# CPLD.net
KiCad netlist of a schematic drawn in Altium Designer
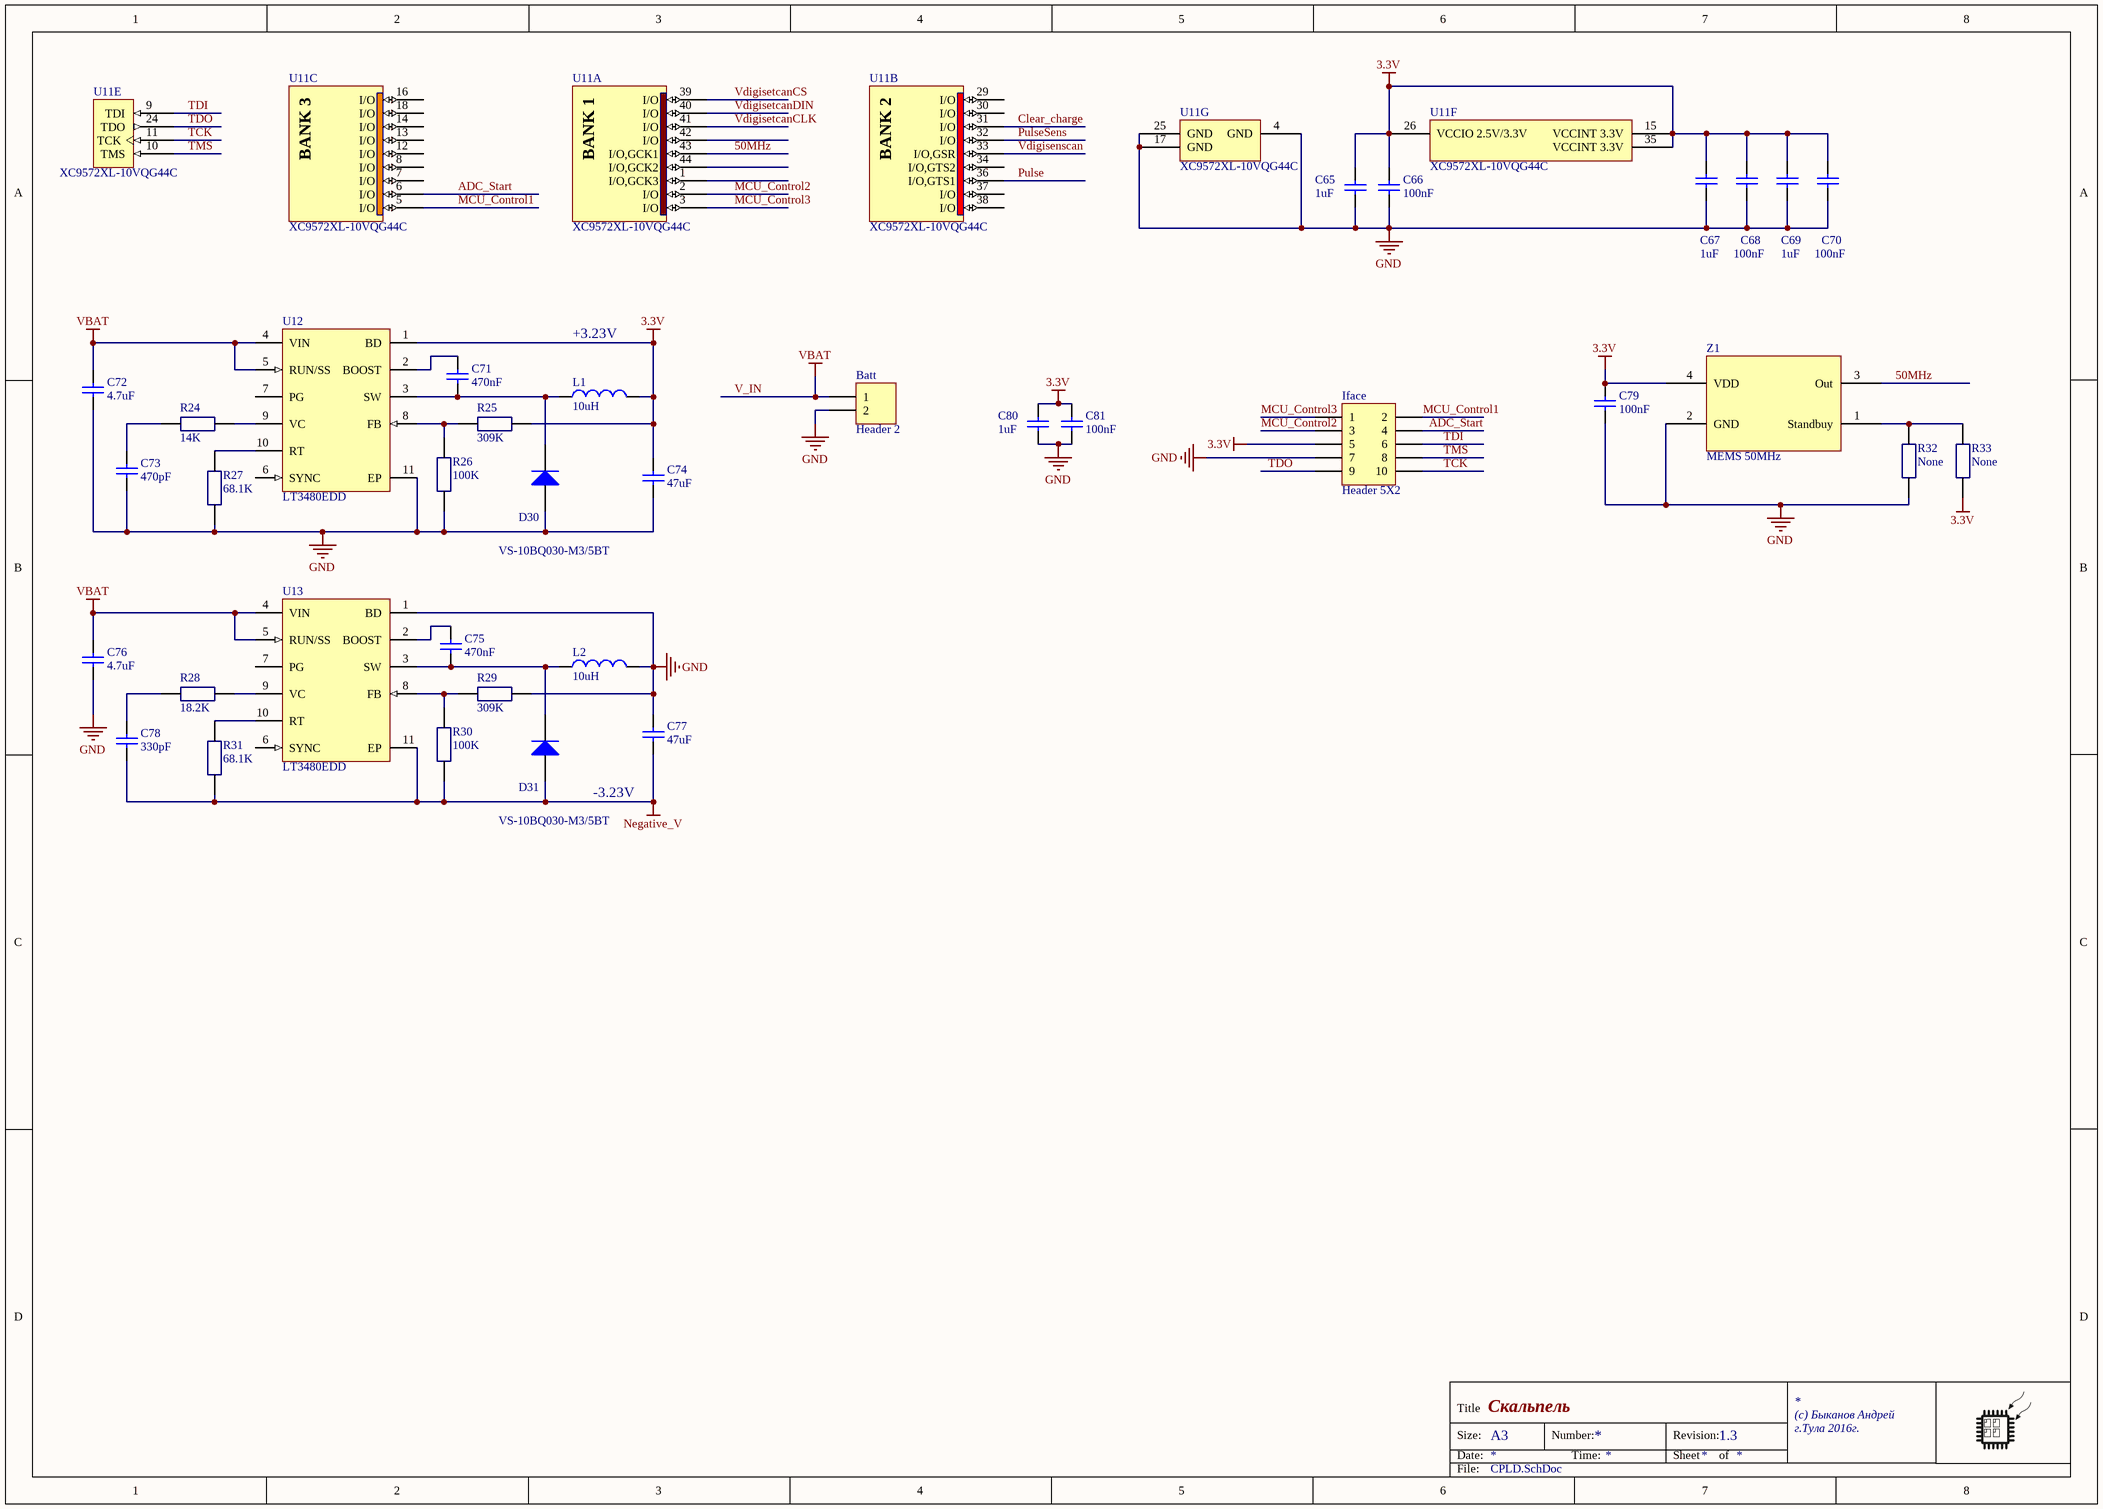
[diagram p0: CPLD.SchDoc]

(export (version "E")
  (design (tool "Eeschema 10.0.6"))
  (components
    (comp (ref "Batt")
      (value "Header 2")
      (footprint "HDR1X2")
      (description "Header, 2-Pin")
      (fields (field (name "PUBLISHER") "Altium Limited"))
      (libsource (lib "Miscellaneous Connectors") (part "Header 2"))
    )
    (comp (ref "C65")
      (value "1uF")
      (footprint "1608[0603]_CAP")
      (description "Capacitor (Semiconductor SIM Model)")
      (fields (field (name "PUBLISHER") "Altium Limited"))
      (libsource (lib "Miscellaneous Devices") (part "Cap Semi"))
    )
    (comp (ref "C66")
      (value "100nF")
      (footprint "1608[0603]_CAP")
      (description "Capacitor (Semiconductor SIM Model)")
      (fields (field (name "PUBLISHER") "Altium Limited"))
      (libsource (lib "Miscellaneous Devices") (part "Cap Semi"))
    )
    (comp (ref "C67")
      (value "1uF")
      (footprint "1608[0603]_CAP")
      (description "Capacitor (Semiconductor SIM Model)")
      (fields (field (name "PUBLISHER") "Altium Limited"))
      (libsource (lib "Miscellaneous Devices") (part "Cap Semi"))
    )
    (comp (ref "C68")
      (value "100nF")
      (footprint "1608[0603]_CAP")
      (description "Capacitor (Semiconductor SIM Model)")
      (fields (field (name "PUBLISHER") "Altium Limited"))
      (libsource (lib "Miscellaneous Devices") (part "Cap Semi"))
    )
    (comp (ref "C69")
      (value "1uF")
      (footprint "1608[0603]_CAP")
      (description "Capacitor (Semiconductor SIM Model)")
      (fields (field (name "PUBLISHER") "Altium Limited"))
      (libsource (lib "Miscellaneous Devices") (part "Cap Semi"))
    )
    (comp (ref "C70")
      (value "100nF")
      (footprint "1608[0603]_CAP")
      (description "Capacitor (Semiconductor SIM Model)")
      (fields (field (name "PUBLISHER") "Altium Limited"))
      (libsource (lib "Miscellaneous Devices") (part "Cap Semi"))
    )
    (comp (ref "C71")
      (value "470nF")
      (footprint "1608[0603]_CAP")
      (description "Capacitor (Semiconductor SIM Model)")
      (fields (field (name "PUBLISHER") "Altium Limited"))
      (libsource (lib "Miscellaneous Devices") (part "Cap Semi"))
    )
    (comp (ref "C72")
      (value "4.7uF")
      (footprint "C1206")
      (description "Capacitor (Semiconductor SIM Model)")
      (fields (field (name "PUBLISHER") "Altium Limited"))
      (libsource (lib "Miscellaneous Devices") (part "Cap Semi"))
    )
    (comp (ref "C73")
      (value "470pF")
      (footprint "1608[0603]_CAP")
      (description "Capacitor (Semiconductor SIM Model)")
      (fields (field (name "PUBLISHER") "Altium Limited"))
      (libsource (lib "Miscellaneous Devices") (part "Cap Semi"))
    )
    (comp (ref "C74")
      (value "47uF")
      (footprint "C1206")
      (description "Capacitor (Semiconductor SIM Model)")
      (fields (field (name "PUBLISHER") "Altium Limited"))
      (libsource (lib "Miscellaneous Devices") (part "Cap Semi"))
    )
    (comp (ref "C75")
      (value "470nF")
      (footprint "1608[0603]_CAP")
      (description "Capacitor (Semiconductor SIM Model)")
      (fields (field (name "PUBLISHER") "Altium Limited"))
      (libsource (lib "Miscellaneous Devices") (part "Cap Semi"))
    )
    (comp (ref "C76")
      (value "4.7uF")
      (footprint "C1206")
      (description "Capacitor (Semiconductor SIM Model)")
      (fields (field (name "PUBLISHER") "Altium Limited"))
      (libsource (lib "Miscellaneous Devices") (part "Cap Semi"))
    )
    (comp (ref "C77")
      (value "47uF")
      (footprint "C1206")
      (description "Capacitor (Semiconductor SIM Model)")
      (fields (field (name "PUBLISHER") "Altium Limited"))
      (libsource (lib "Miscellaneous Devices") (part "Cap Semi"))
    )
    (comp (ref "C78")
      (value "330pF")
      (footprint "1608[0603]_CAP")
      (description "Capacitor (Semiconductor SIM Model)")
      (fields (field (name "PUBLISHER") "Altium Limited"))
      (libsource (lib "Miscellaneous Devices") (part "Cap Semi"))
    )
    (comp (ref "C79")
      (value "100nF")
      (footprint "1608[0603]_CAP")
      (description "Capacitor (Semiconductor SIM Model)")
      (fields (field (name "PUBLISHER") "Altium Limited"))
      (libsource (lib "Miscellaneous Devices") (part "Cap Semi"))
    )
    (comp (ref "C80")
      (value "1uF")
      (footprint "1608[0603]_CAP")
      (description "Capacitor (Semiconductor SIM Model)")
      (fields (field (name "PUBLISHER") "Altium Limited"))
      (libsource (lib "Miscellaneous Devices") (part "Cap Semi"))
    )
    (comp (ref "C81")
      (value "100nF")
      (footprint "1608[0603]_CAP")
      (description "Capacitor (Semiconductor SIM Model)")
      (fields (field (name "PUBLISHER") "Altium Limited"))
      (libsource (lib "Miscellaneous Devices") (part "Cap Semi"))
    )
    (comp (ref "D30")
      (value "VS-10BQ030-M3/5BT")
      (footprint "SMB")
      (description "Default Diode")
      (fields (field (name "PUBLISHER") "Altium Limited"))
      (libsource (lib "Miscellaneous Devices") (part "Diode"))
    )
    (comp (ref "D31")
      (value "VS-10BQ030-M3/5BT")
      (footprint "SMB")
      (description "Default Diode")
      (fields (field (name "PUBLISHER") "Altium Limited"))
      (libsource (lib "Miscellaneous Devices") (part "Diode"))
    )
    (comp (ref "Iface")
      (value "Header 5X2")
      (footprint "HDR2X5")
      (description "Header, 5-Pin, Dual row")
      (fields (field (name "PUBLISHER") "Altium Limited"))
      (libsource (lib "Miscellaneous Connectors") (part "Header 5X2"))
    )
    (comp (ref "L1")
      (value "10uH")
      (footprint "SLF10145")
      (description "Inductor")
      (fields (field (name "PUBLISHER") "Altium Limited"))
      (libsource (lib "Miscellaneous Devices") (part "Inductor"))
    )
    (comp (ref "L2")
      (value "10uH")
      (footprint "SLF10145")
      (description "Inductor")
      (fields (field (name "PUBLISHER") "Altium Limited"))
      (libsource (lib "Miscellaneous Devices") (part "Inductor"))
    )
    (comp (ref "R24")
      (value "14K")
      (footprint "1608[0603]_RES")
      (libsource (lib "Микрон-3") (part "Resistor 0805"))
    )
    (comp (ref "R25")
      (value "309K")
      (footprint "1608[0603]_RES")
      (libsource (lib "Микрон-3") (part "Resistor 0805"))
    )
    (comp (ref "R26")
      (value "100K")
      (footprint "1608[0603]_RES")
      (libsource (lib "Микрон-3") (part "Resistor 0805"))
    )
    (comp (ref "R27")
      (value "68.1K")
      (footprint "1608[0603]_RES")
      (libsource (lib "Микрон-3") (part "Resistor 0805"))
    )
    (comp (ref "R28")
      (value "18.2K")
      (footprint "1608[0603]_RES")
      (libsource (lib "Микрон-3") (part "Resistor 0805"))
    )
    (comp (ref "R29")
      (value "309K")
      (footprint "1608[0603]_RES")
      (libsource (lib "Микрон-3") (part "Resistor 0805"))
    )
    (comp (ref "R30")
      (value "100K")
      (footprint "1608[0603]_RES")
      (libsource (lib "Микрон-3") (part "Resistor 0805"))
    )
    (comp (ref "R31")
      (value "68.1K")
      (footprint "1608[0603]_RES")
      (libsource (lib "Микрон-3") (part "Resistor 0805"))
    )
    (comp (ref "R32")
      (value "None")
      (footprint "0402 Yageo")
      (libsource (lib "Микрон-3") (part "Resistor 0805"))
    )
    (comp (ref "R33")
      (value "None")
      (footprint "0402 Yageo")
      (libsource (lib "Микрон-3") (part "Resistor 0805"))
    )
    (comp (ref "U11")
      (value "XC9572XL-10VQG44C")
      (footprint "VQG44_N")
      (fields (field (name "PUBLISHER") "Altium Limited"))
      (libsource (lib "Xilinx XC9500XL") (part "XC9572XL-10VQG44C"))
    )
    (comp (ref "U12")
      (value "LT3480EDD")
      (footprint "LT-DD-10_V")
      (fields (field (name "MANUFACTURER") "Linear Technology") (field (name "PARTNUMBER") "LT3480EDD#PBF"))
      (libsource (lib "Linear Technology Power Management Switching Regulator LT1074-LT8705") (part "LT3480EDD#PBF"))
    )
    (comp (ref "U13")
      (value "LT3480EDD")
      (footprint "LT-DD-10_V")
      (fields (field (name "MANUFACTURER") "Linear Technology") (field (name "PARTNUMBER") "LT3480EDD#PBF"))
      (libsource (lib "Linear Technology Power Management Switching Regulator LT1074-LT8705") (part "LT3480EDD#PBF"))
    )
    (comp (ref "Z1")
      (value "MEMS 50MHz")
      (footprint "asdmb")
      (libsource (lib "My SCH library") (part "ASEMB"))
    )
  )
  (nets
    (net (code "1") (name "/50MHz") (class "Default")
      (node (ref "U11") (pin "43") (pinfunction "I/O,GCK1_43") (pintype "bidirectional"))
      (node (ref "Z1") (pin "3") (pinfunction "Out_3") (pintype "passive"))
    )
    (net (code "2") (name "/ADC_Start") (class "Default")
      (node (ref "Iface") (pin "4") (pinfunction "4_4") (pintype "passive"))
      (node (ref "U11") (pin "6") (pinfunction "I/O_6") (pintype "bidirectional"))
    )
    (net (code "3") (name "/Clear_charge") (class "Default")
      (node (ref "U11") (pin "31") (pinfunction "I/O_31") (pintype "bidirectional"))
    )
    (net (code "4") (name "/MCU_Control1") (class "Default")
      (node (ref "Iface") (pin "2") (pinfunction "2_2") (pintype "passive"))
      (node (ref "U11") (pin "5") (pinfunction "I/O_5") (pintype "bidirectional"))
    )
    (net (code "5") (name "/MCU_Control2") (class "Default")
      (node (ref "Iface") (pin "3") (pinfunction "3_3") (pintype "passive"))
      (node (ref "U11") (pin "2") (pinfunction "I/O_2") (pintype "bidirectional"))
    )
    (net (code "6") (name "/MCU_Control3") (class "Default")
      (node (ref "Iface") (pin "1") (pinfunction "1_1") (pintype "passive"))
      (node (ref "U11") (pin "3") (pinfunction "I/O_3") (pintype "bidirectional"))
    )
    (net (code "7") (name "/Pulse") (class "Default")
      (node (ref "U11") (pin "36") (pinfunction "I/O,GTS1_36") (pintype "bidirectional"))
    )
    (net (code "8") (name "/PulseSens") (class "Default")
      (node (ref "U11") (pin "32") (pinfunction "I/O_32") (pintype "bidirectional"))
    )
    (net (code "9") (name "/TCK") (class "Default")
      (node (ref "Iface") (pin "10") (pinfunction "10_10") (pintype "passive"))
      (node (ref "U11") (pin "11") (pinfunction "TCK_11") (pintype "input"))
    )
    (net (code "10") (name "/TDI") (class "Default")
      (node (ref "Iface") (pin "6") (pinfunction "6_6") (pintype "passive"))
      (node (ref "U11") (pin "9") (pinfunction "TDI_9") (pintype "input"))
    )
    (net (code "11") (name "/TDO") (class "Default")
      (node (ref "Iface") (pin "9") (pinfunction "9_9") (pintype "passive"))
      (node (ref "U11") (pin "24") (pinfunction "TDO_24") (pintype "output"))
    )
    (net (code "12") (name "/TMS") (class "Default")
      (node (ref "Iface") (pin "8") (pinfunction "8_8") (pintype "passive"))
      (node (ref "U11") (pin "10") (pinfunction "TMS_10") (pintype "input"))
    )
    (net (code "13") (name "/Vdigisenscan") (class "Default")
      (node (ref "U11") (pin "33") (pinfunction "I/O,GSR_33") (pintype "bidirectional"))
    )
    (net (code "14") (name "/VdigisetcanCLK") (class "Default")
      (node (ref "U11") (pin "41") (pinfunction "I/O_41") (pintype "bidirectional"))
    )
    (net (code "15") (name "/VdigisetcanCS") (class "Default")
      (node (ref "U11") (pin "39") (pinfunction "I/O_39") (pintype "bidirectional"))
    )
    (net (code "16") (name "/VdigisetcanDIN") (class "Default")
      (node (ref "U11") (pin "40") (pinfunction "I/O_40") (pintype "bidirectional"))
    )
    (net (code "17") (name "3.3V") (class "Default")
      (node (ref "C65") (pin "1") (pinfunction "1_1") (pintype "passive"))
      (node (ref "C66") (pin "1") (pinfunction "1_1") (pintype "passive"))
      (node (ref "C67") (pin "1") (pinfunction "1_1") (pintype "passive"))
      (node (ref "C68") (pin "1") (pinfunction "1_1") (pintype "passive"))
      (node (ref "C69") (pin "1") (pinfunction "1_1") (pintype "passive"))
      (node (ref "C70") (pin "1") (pinfunction "1_1") (pintype "passive"))
      (node (ref "C74") (pin "1") (pinfunction "1_1") (pintype "passive"))
      (node (ref "C79") (pin "1") (pinfunction "1_1") (pintype "passive"))
      (node (ref "C80") (pin "1") (pinfunction "1_1") (pintype "passive"))
      (node (ref "C81") (pin "1") (pinfunction "1_1") (pintype "passive"))
      (node (ref "Iface") (pin "5") (pinfunction "5_5") (pintype "passive"))
      (node (ref "L1") (pin "2") (pinfunction "2_2") (pintype "passive"))
      (node (ref "R25") (pin "2") (pinfunction "2_2") (pintype "passive"))
      (node (ref "R33") (pin "1") (pinfunction "A_1") (pintype "passive"))
      (node (ref "U11") (pin "15") (pinfunction "VCCINT_3.3V_15") (pintype "power_in"))
      (node (ref "U11") (pin "26") (pinfunction "VCCIO_2.5V/3.3V_26") (pintype "power_in"))
      (node (ref "U11") (pin "35") (pinfunction "VCCINT_3.3V_35") (pintype "power_in"))
      (node (ref "U12") (pin "1") (pinfunction "BD_1") (pintype "power_in"))
      (node (ref "Z1") (pin "4") (pinfunction "VDD_4") (pintype "passive"))
    )
    (net (code "18") (name "GND") (class "Default")
      (node (ref "Batt") (pin "2") (pinfunction "2_2") (pintype "passive"))
      (node (ref "C65") (pin "2") (pinfunction "2_2") (pintype "passive"))
      (node (ref "C66") (pin "2") (pinfunction "2_2") (pintype "passive"))
      (node (ref "C67") (pin "2") (pinfunction "2_2") (pintype "passive"))
      (node (ref "C68") (pin "2") (pinfunction "2_2") (pintype "passive"))
      (node (ref "C69") (pin "2") (pinfunction "2_2") (pintype "passive"))
      (node (ref "C70") (pin "2") (pinfunction "2_2") (pintype "passive"))
      (node (ref "C72") (pin "2") (pinfunction "2_2") (pintype "passive"))
      (node (ref "C73") (pin "2") (pinfunction "2_2") (pintype "passive"))
      (node (ref "C74") (pin "2") (pinfunction "2_2") (pintype "passive"))
      (node (ref "C76") (pin "2") (pinfunction "2_2") (pintype "passive"))
      (node (ref "C77") (pin "1") (pinfunction "1_1") (pintype "passive"))
      (node (ref "C79") (pin "2") (pinfunction "2_2") (pintype "passive"))
      (node (ref "C80") (pin "2") (pinfunction "2_2") (pintype "passive"))
      (node (ref "C81") (pin "2") (pinfunction "2_2") (pintype "passive"))
      (node (ref "D30") (pin "1") (pinfunction "A_1") (pintype "passive"))
      (node (ref "Iface") (pin "7") (pinfunction "7_7") (pintype "passive"))
      (node (ref "L2") (pin "2") (pinfunction "2_2") (pintype "passive"))
      (node (ref "R26") (pin "1") (pinfunction "A_1") (pintype "passive"))
      (node (ref "R27") (pin "1") (pinfunction "A_1") (pintype "passive"))
      (node (ref "R29") (pin "2") (pinfunction "2_2") (pintype "passive"))
      (node (ref "R32") (pin "1") (pinfunction "A_1") (pintype "passive"))
      (node (ref "U11") (pin "17") (pinfunction "GND_17") (pintype "power_in"))
      (node (ref "U11") (pin "25") (pinfunction "GND_25") (pintype "power_in"))
      (node (ref "U11") (pin "4") (pinfunction "GND_4") (pintype "power_in"))
      (node (ref "U12") (pin "11") (pinfunction "EP_11") (pintype "power_in"))
      (node (ref "U13") (pin "1") (pinfunction "BD_1") (pintype "power_in"))
      (node (ref "Z1") (pin "2") (pinfunction "GND_2") (pintype "passive"))
    )
    (net (code "19") (name "Negative_V") (class "Default")
      (node (ref "C77") (pin "2") (pinfunction "2_2") (pintype "passive"))
      (node (ref "C78") (pin "2") (pinfunction "2_2") (pintype "passive"))
      (node (ref "D31") (pin "1") (pinfunction "A_1") (pintype "passive"))
      (node (ref "R30") (pin "1") (pinfunction "A_1") (pintype "passive"))
      (node (ref "R31") (pin "1") (pinfunction "A_1") (pintype "passive"))
      (node (ref "U13") (pin "11") (pinfunction "EP_11") (pintype "power_in"))
    )
    (net (code "20") (name "Net-(D30-K)") (class "Default")
      (node (ref "C71") (pin "2") (pinfunction "2_2") (pintype "passive"))
      (node (ref "D30") (pin "2") (pinfunction "K_2") (pintype "passive"))
      (node (ref "L1") (pin "1") (pinfunction "1_1") (pintype "passive"))
      (node (ref "U12") (pin "3") (pinfunction "SW_3") (pintype "power_in"))
    )
    (net (code "21") (name "Net-(D31-K)") (class "Default")
      (node (ref "C75") (pin "2") (pinfunction "2_2") (pintype "passive"))
      (node (ref "D31") (pin "2") (pinfunction "K_2") (pintype "passive"))
      (node (ref "L2") (pin "1") (pinfunction "1_1") (pintype "passive"))
      (node (ref "U13") (pin "3") (pinfunction "SW_3") (pintype "power_in"))
    )
    (net (code "22") (name "Net-(R24-A)") (class "Default")
      (node (ref "C73") (pin "1") (pinfunction "1_1") (pintype "passive"))
      (node (ref "R24") (pin "1") (pinfunction "A_1") (pintype "passive"))
    )
    (net (code "23") (name "Net-(R25-A)") (class "Default")
      (node (ref "R25") (pin "1") (pinfunction "A_1") (pintype "passive"))
      (node (ref "R26") (pin "2") (pinfunction "2_2") (pintype "passive"))
      (node (ref "U12") (pin "8") (pinfunction "FB_8") (pintype "input"))
    )
    (net (code "24") (name "Net-(R28-A)") (class "Default")
      (node (ref "C78") (pin "1") (pinfunction "1_1") (pintype "passive"))
      (node (ref "R28") (pin "1") (pinfunction "A_1") (pintype "passive"))
    )
    (net (code "25") (name "Net-(R29-A)") (class "Default")
      (node (ref "R29") (pin "1") (pinfunction "A_1") (pintype "passive"))
      (node (ref "R30") (pin "2") (pinfunction "2_2") (pintype "passive"))
      (node (ref "U13") (pin "8") (pinfunction "FB_8") (pintype "input"))
    )
    (net (code "26") (name "Net-(U12-BOOST)") (class "Default")
      (node (ref "C71") (pin "1") (pinfunction "1_1") (pintype "passive"))
      (node (ref "U12") (pin "2") (pinfunction "BOOST_2") (pintype "passive"))
    )
    (net (code "27") (name "Net-(U12-RT)") (class "Default")
      (node (ref "R27") (pin "2") (pinfunction "2_2") (pintype "passive"))
      (node (ref "U12") (pin "10") (pinfunction "RT_10") (pintype "passive"))
    )
    (net (code "28") (name "Net-(U12-VC)") (class "Default")
      (node (ref "R24") (pin "2") (pinfunction "2_2") (pintype "passive"))
      (node (ref "U12") (pin "9") (pinfunction "VC_9") (pintype "passive"))
    )
    (net (code "29") (name "Net-(U13-BOOST)") (class "Default")
      (node (ref "C75") (pin "1") (pinfunction "1_1") (pintype "passive"))
      (node (ref "U13") (pin "2") (pinfunction "BOOST_2") (pintype "passive"))
    )
    (net (code "30") (name "Net-(U13-RT)") (class "Default")
      (node (ref "R31") (pin "2") (pinfunction "2_2") (pintype "passive"))
      (node (ref "U13") (pin "10") (pinfunction "RT_10") (pintype "passive"))
    )
    (net (code "31") (name "Net-(U13-VC)") (class "Default")
      (node (ref "R28") (pin "2") (pinfunction "2_2") (pintype "passive"))
      (node (ref "U13") (pin "9") (pinfunction "VC_9") (pintype "passive"))
    )
    (net (code "32") (name "Net-(Z1-Standbuy)") (class "Default")
      (node (ref "R32") (pin "2") (pinfunction "2_2") (pintype "passive"))
      (node (ref "R33") (pin "2") (pinfunction "2_2") (pintype "passive"))
      (node (ref "Z1") (pin "1") (pinfunction "Standbuy_1") (pintype "passive"))
    )
    (net (code "33") (name "VBAT") (class "Default")
      (node (ref "Batt") (pin "1") (pinfunction "1_1") (pintype "passive"))
      (node (ref "C72") (pin "1") (pinfunction "1_1") (pintype "passive"))
      (node (ref "C76") (pin "1") (pinfunction "1_1") (pintype "passive"))
      (node (ref "U12") (pin "4") (pinfunction "VIN_4") (pintype "power_in"))
      (node (ref "U12") (pin "5") (pinfunction "RUN/SS_5") (pintype "input"))
      (node (ref "U13") (pin "4") (pinfunction "VIN_4") (pintype "power_in"))
      (node (ref "U13") (pin "5") (pinfunction "RUN/SS_5") (pintype "input"))
    )
    (net (code "34") (name "unconnected-(U11A-I{slash}O,GCK2-Pad44)") (class "Default")
      (node (ref "U11") (pin "44") (pinfunction "I/O,GCK2_44") (pintype "bidirectional"))
    )
    (net (code "35") (name "unconnected-(U11A-I{slash}O,GCK3-Pad1)") (class "Default")
      (node (ref "U11") (pin "1") (pinfunction "I/O,GCK3_1") (pintype "bidirectional"))
    )
    (net (code "36") (name "unconnected-(U11A-I{slash}O-Pad42)") (class "Default")
      (node (ref "U11") (pin "42") (pinfunction "I/O_42") (pintype "bidirectional"))
    )
    (net (code "37") (name "unconnected-(U11B-I{slash}O,GTS2-Pad34)") (class "Default")
      (node (ref "U11") (pin "34") (pinfunction "I/O,GTS2_34") (pintype "bidirectional"))
    )
    (net (code "38") (name "unconnected-(U11B-I{slash}O-Pad29)") (class "Default")
      (node (ref "U11") (pin "29") (pinfunction "I/O_29") (pintype "bidirectional"))
    )
    (net (code "39") (name "unconnected-(U11B-I{slash}O-Pad30)") (class "Default")
      (node (ref "U11") (pin "30") (pinfunction "I/O_30") (pintype "bidirectional"))
    )
    (net (code "40") (name "unconnected-(U11B-I{slash}O-Pad37)") (class "Default")
      (node (ref "U11") (pin "37") (pinfunction "I/O_37") (pintype "bidirectional"))
    )
    (net (code "41") (name "unconnected-(U11B-I{slash}O-Pad38)") (class "Default")
      (node (ref "U11") (pin "38") (pinfunction "I/O_38") (pintype "bidirectional"))
    )
    (net (code "42") (name "unconnected-(U11C-I{slash}O-Pad7)") (class "Default")
      (node (ref "U11") (pin "7") (pinfunction "I/O_7") (pintype "bidirectional"))
    )
    (net (code "43") (name "unconnected-(U11C-I{slash}O-Pad8)") (class "Default")
      (node (ref "U11") (pin "8") (pinfunction "I/O_8") (pintype "bidirectional"))
    )
    (net (code "44") (name "unconnected-(U11C-I{slash}O-Pad12)") (class "Default")
      (node (ref "U11") (pin "12") (pinfunction "I/O_12") (pintype "bidirectional"))
    )
    (net (code "45") (name "unconnected-(U11C-I{slash}O-Pad13)") (class "Default")
      (node (ref "U11") (pin "13") (pinfunction "I/O_13") (pintype "bidirectional"))
    )
    (net (code "46") (name "unconnected-(U11C-I{slash}O-Pad14)") (class "Default")
      (node (ref "U11") (pin "14") (pinfunction "I/O_14") (pintype "bidirectional"))
    )
    (net (code "47") (name "unconnected-(U11C-I{slash}O-Pad16)") (class "Default")
      (node (ref "U11") (pin "16") (pinfunction "I/O_16") (pintype "bidirectional"))
    )
    (net (code "48") (name "unconnected-(U11C-I{slash}O-Pad18)") (class "Default")
      (node (ref "U11") (pin "18") (pinfunction "I/O_18") (pintype "bidirectional"))
    )
    (net (code "49") (name "unconnected-(U12-PG-Pad7)") (class "Default")
      (node (ref "U12") (pin "7") (pinfunction "PG_7") (pintype "open_collector"))
    )
    (net (code "50") (name "unconnected-(U12-SYNC-Pad6)") (class "Default")
      (node (ref "U12") (pin "6") (pinfunction "SYNC_6") (pintype "input"))
    )
    (net (code "51") (name "unconnected-(U13-PG-Pad7)") (class "Default")
      (node (ref "U13") (pin "7") (pinfunction "PG_7") (pintype "open_collector"))
    )
    (net (code "52") (name "unconnected-(U13-SYNC-Pad6)") (class "Default")
      (node (ref "U13") (pin "6") (pinfunction "SYNC_6") (pintype "input"))
    )
  )
)
